# FSQCallTelemetry.net
KiCad netlist of a schematic drawn in EAGLE
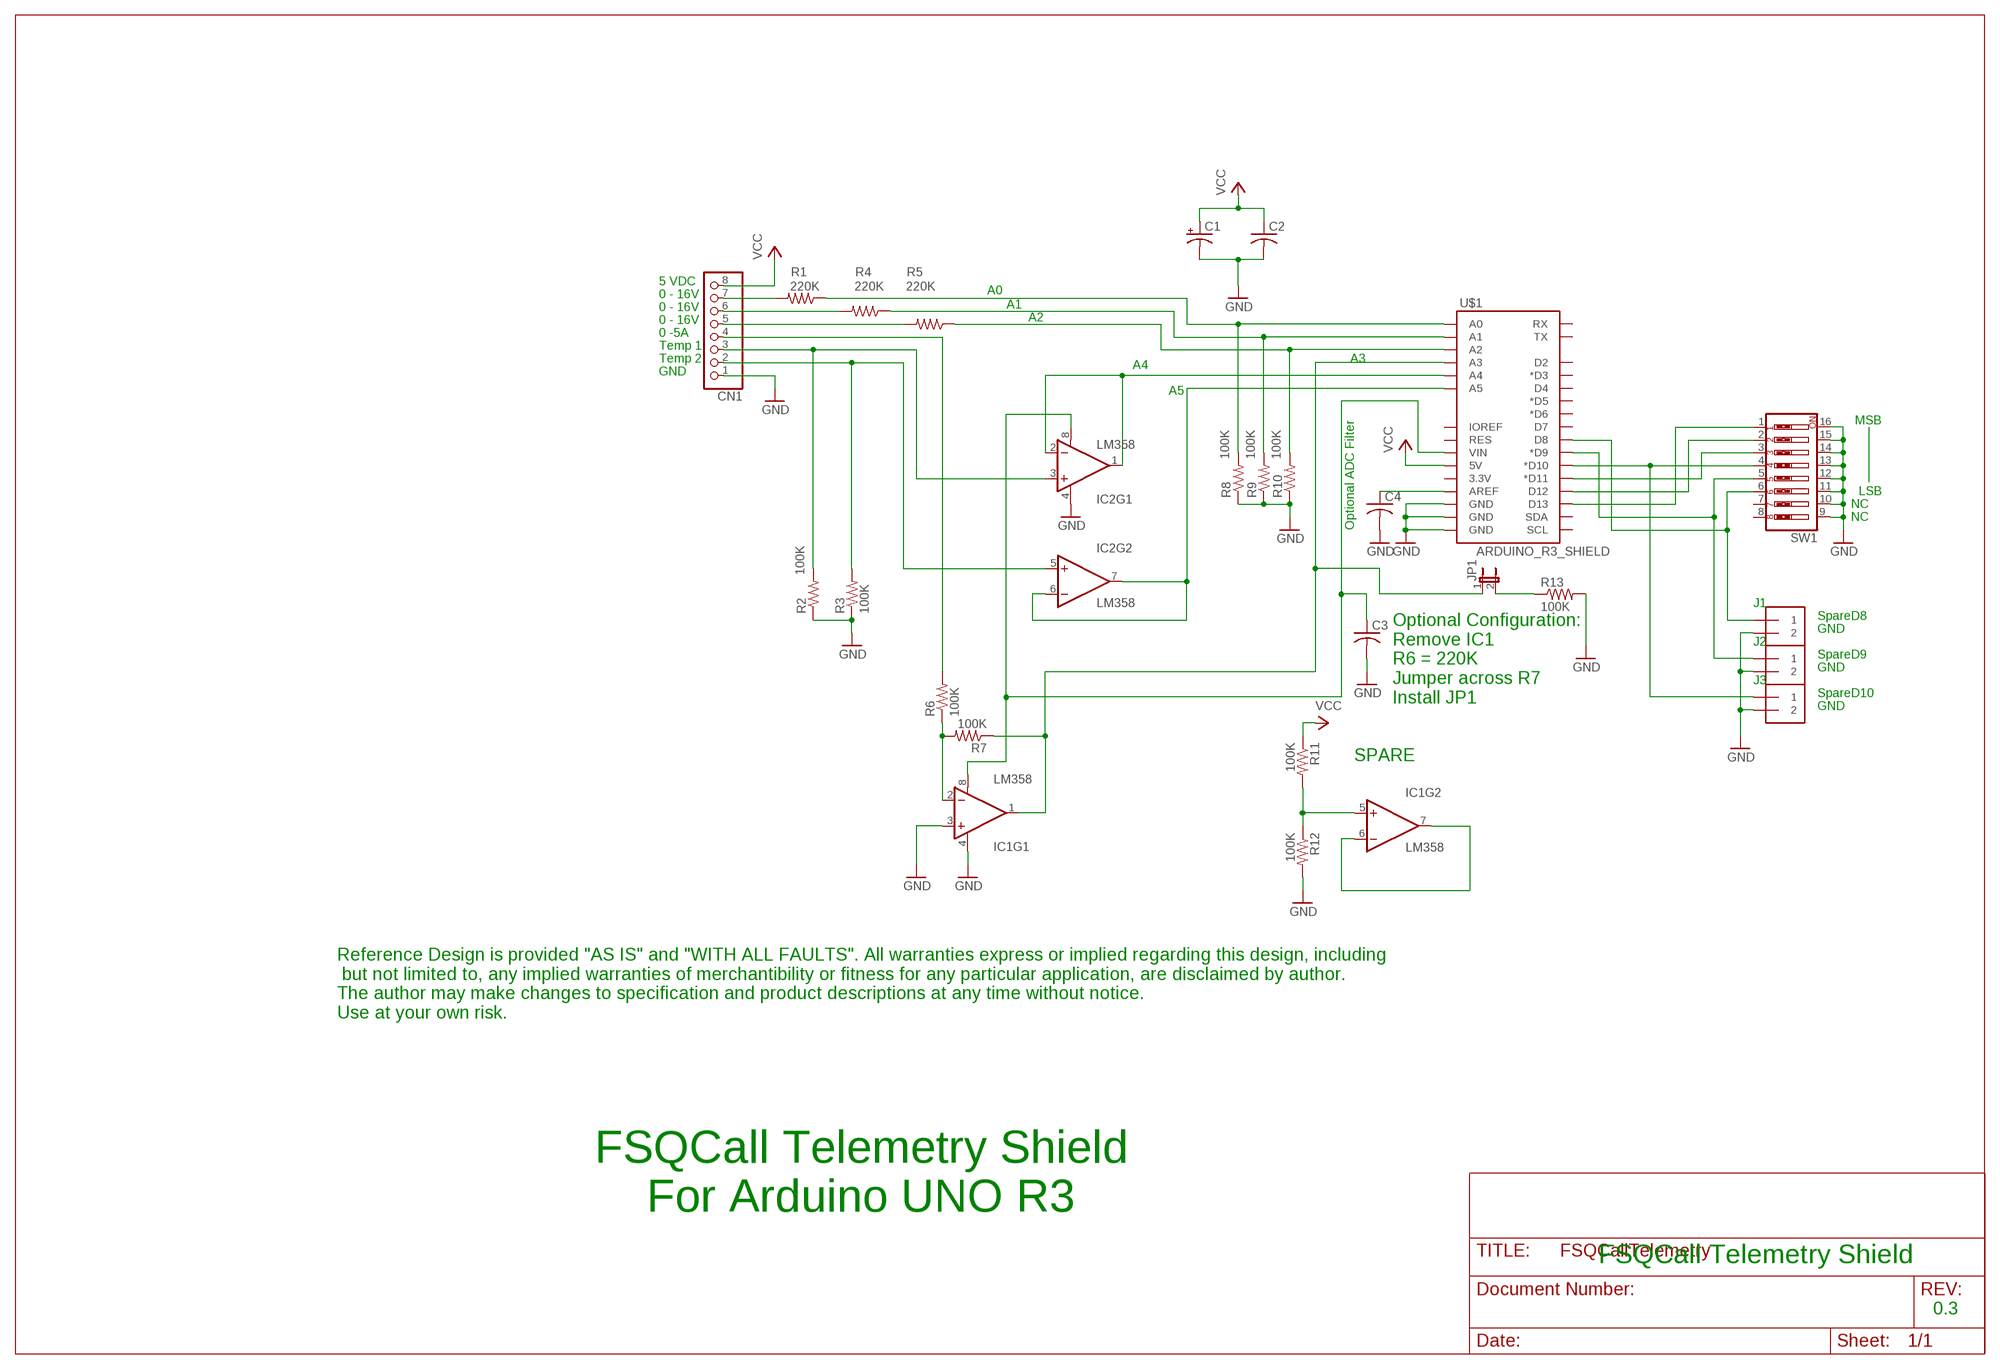
[diagram p0: schematic, sheet 1]

(export (version "E")
  (design (tool "Eeschema 10.0.6"))
  (components
    (comp (ref "C1")
      (value "CPOL-USTT6D6")
      (footprint "eagle-import:TT5D6")
      (libsource (lib "eagle-import") (part "CPOL-USTT6D6"))
    )
    (comp (ref "C2")
      (value "C-US050-025X075")
      (footprint "eagle-import:C050-025X075")
      (libsource (lib "eagle-import") (part "C-US050-025X075"))
    )
    (comp (ref "C3")
      (value "C-US050-025X075")
      (footprint "eagle-import:C050-025X075")
      (libsource (lib "eagle-import") (part "C-US050-025X075"))
    )
    (comp (ref "C4")
      (value "C-US050-025X075")
      (footprint "eagle-import:C050-025X075")
      (libsource (lib "eagle-import") (part "C-US050-025X075"))
    )
    (comp (ref "CN1")
      (value "PINHD-1X8BIG")
      (footprint "eagle-import:1X08-BIG")
      (libsource (lib "eagle-import") (part "PINHD-1X8BIG"))
    )
    (comp (ref "IC1")
      (value "LM358")
      (footprint "eagle-import:DIP08")
      (libsource (lib "eagle-import") (part "LM358"))
    )
    (comp (ref "IC2")
      (value "LM358")
      (footprint "eagle-import:DIP08")
      (libsource (lib "eagle-import") (part "LM358"))
    )
    (comp (ref "J1")
      (value "1X2-3.5MM")
      (footprint "eagle-import:1X2-3.5MM")
      (libsource (lib "eagle-import") (part "1X2-3.5MM"))
    )
    (comp (ref "J2")
      (value "1X2-3.5MM")
      (footprint "eagle-import:1X2-3.5MM")
      (libsource (lib "eagle-import") (part "1X2-3.5MM"))
    )
    (comp (ref "J3")
      (value "1X2-3.5MM")
      (footprint "eagle-import:1X2-3.5MM")
      (libsource (lib "eagle-import") (part "1X2-3.5MM"))
    )
    (comp (ref "JP1")
      (value "JP1E")
      (footprint "eagle-import:JP1")
      (libsource (lib "eagle-import") (part "JP1E"))
    )
    (comp (ref "R1")
      (value "220K")
      (footprint "eagle-import:0207_10")
      (libsource (lib "eagle-import") (part "R-US_0207/10"))
    )
    (comp (ref "R2")
      (value "100K")
      (footprint "eagle-import:0207_10")
      (libsource (lib "eagle-import") (part "R-US_0207/10"))
    )
    (comp (ref "R3")
      (value "100K")
      (footprint "eagle-import:0207_10")
      (libsource (lib "eagle-import") (part "R-US_0207/10"))
    )
    (comp (ref "R4")
      (value "220K")
      (footprint "eagle-import:0207_10")
      (libsource (lib "eagle-import") (part "R-US_0207/10"))
    )
    (comp (ref "R5")
      (value "220K")
      (footprint "eagle-import:0207_10")
      (libsource (lib "eagle-import") (part "R-US_0207/10"))
    )
    (comp (ref "R6")
      (value "100K")
      (footprint "eagle-import:0207_10")
      (libsource (lib "eagle-import") (part "R-US_0207/10"))
    )
    (comp (ref "R7")
      (value "100K")
      (footprint "eagle-import:0207_10")
      (libsource (lib "eagle-import") (part "R-US_0207/10"))
    )
    (comp (ref "R8")
      (value "100K")
      (footprint "eagle-import:0207_10")
      (libsource (lib "eagle-import") (part "R-US_0207/10"))
    )
    (comp (ref "R9")
      (value "100K")
      (footprint "eagle-import:0207_10")
      (libsource (lib "eagle-import") (part "R-US_0207/10"))
    )
    (comp (ref "R10")
      (value "100K")
      (footprint "eagle-import:0207_10")
      (libsource (lib "eagle-import") (part "R-US_0207/10"))
    )
    (comp (ref "R11")
      (value "100K")
      (footprint "eagle-import:0207_10")
      (libsource (lib "eagle-import") (part "R-US_0207/10"))
    )
    (comp (ref "R12")
      (value "100K")
      (footprint "eagle-import:0207_10")
      (libsource (lib "eagle-import") (part "R-US_0207/10"))
    )
    (comp (ref "R13")
      (value "100K")
      (footprint "eagle-import:0207_10")
      (libsource (lib "eagle-import") (part "R-US_0207/10"))
    )
    (comp (ref "SW1")
      (value "SW_DIP-8")
      (footprint "eagle-import:DIPSWITCH-08")
      (libsource (lib "eagle-import") (part "SW_DIP-8"))
    )
    (comp (ref "U$1")
      (value "ARDUINO_R3_SHIELD")
      (footprint "eagle-import:UNO_R3_SHIELD")
      (libsource (lib "eagle-import") (part "ARDUINO_R3_SHIELD"))
    )
  )
  (nets
    (net (code "1") (name "GND") (class "Default")
      (node (ref "C1") (pin "-") (pinfunction "-_-") (pintype "passive"))
      (node (ref "C2") (pin "2") (pinfunction "2_2") (pintype "passive"))
      (node (ref "C3") (pin "2") (pinfunction "2_2") (pintype "passive"))
      (node (ref "C4") (pin "2") (pinfunction "2_2") (pintype "passive"))
      (node (ref "CN1") (pin "1") (pinfunction "1_1") (pintype "passive"))
      (node (ref "IC1") (pin "3") (pinfunction "+IN_3") (pintype "input"))
      (node (ref "IC1") (pin "4") (pinfunction "V-_4") (pintype "power_in"))
      (node (ref "IC2") (pin "4") (pinfunction "V-_4") (pintype "power_in"))
      (node (ref "J1") (pin "2") (pinfunction "2_2") (pintype "passive"))
      (node (ref "J2") (pin "2") (pinfunction "2_2") (pintype "passive"))
      (node (ref "J3") (pin "2") (pinfunction "2_2") (pintype "passive"))
      (node (ref "R10") (pin "1") (pinfunction "1_1") (pintype "passive"))
      (node (ref "R12") (pin "2") (pinfunction "2_2") (pintype "passive"))
      (node (ref "R13") (pin "2") (pinfunction "2_2") (pintype "passive"))
      (node (ref "R2") (pin "1") (pinfunction "1_1") (pintype "passive"))
      (node (ref "R3") (pin "1") (pinfunction "1_1") (pintype "passive"))
      (node (ref "R8") (pin "1") (pinfunction "1_1") (pintype "passive"))
      (node (ref "R9") (pin "1") (pinfunction "1_1") (pintype "passive"))
      (node (ref "SW1") (pin "10") (pinfunction "10_10") (pintype "passive"))
      (node (ref "SW1") (pin "11") (pinfunction "11_11") (pintype "passive"))
      (node (ref "SW1") (pin "12") (pinfunction "12_12") (pintype "passive"))
      (node (ref "SW1") (pin "13") (pinfunction "13_13") (pintype "passive"))
      (node (ref "SW1") (pin "14") (pinfunction "14_14") (pintype "passive"))
      (node (ref "SW1") (pin "15") (pinfunction "15_15") (pintype "passive"))
      (node (ref "SW1") (pin "16") (pinfunction "16_16") (pintype "passive"))
      (node (ref "SW1") (pin "9") (pinfunction "9_9") (pintype "passive"))
      (node (ref "U$1") (pin "GND@0") (pinfunction "GND_GND@0") (pintype "bidirectional"))
      (node (ref "U$1") (pin "GND@1") (pinfunction "GND_GND@1") (pintype "bidirectional"))
      (node (ref "U$1") (pin "GND@2") (pinfunction "GND_GND@2") (pintype "bidirectional"))
    )
    (net (code "2") (name "Net-(C4-Pad1)") (class "Default")
      (node (ref "C4") (pin "1") (pinfunction "1_1") (pintype "passive"))
      (node (ref "U$1") (pin "AREF") (pinfunction "AREF_AREF") (pintype "bidirectional"))
    )
    (net (code "3") (name "Net-(CN1-Pad4)") (class "Default")
      (node (ref "CN1") (pin "4") (pinfunction "4_4") (pintype "passive"))
      (node (ref "R6") (pin "2") (pinfunction "2_2") (pintype "passive"))
    )
    (net (code "4") (name "Net-(CN1-Pad5)") (class "Default")
      (node (ref "CN1") (pin "5") (pinfunction "5_5") (pintype "passive"))
      (node (ref "R5") (pin "2") (pinfunction "2_2") (pintype "passive"))
    )
    (net (code "5") (name "Net-(CN1-Pad6)") (class "Default")
      (node (ref "CN1") (pin "6") (pinfunction "6_6") (pintype "passive"))
      (node (ref "R4") (pin "2") (pinfunction "2_2") (pintype "passive"))
    )
    (net (code "6") (name "Net-(CN1-Pad7)") (class "Default")
      (node (ref "CN1") (pin "7") (pinfunction "7_7") (pintype "passive"))
      (node (ref "R1") (pin "2") (pinfunction "2_2") (pintype "passive"))
    )
    (net (code "7") (name "Net-(IC1A--IN)") (class "Default")
      (node (ref "IC1") (pin "2") (pinfunction "-IN_2") (pintype "input"))
      (node (ref "R6") (pin "1") (pinfunction "1_1") (pintype "passive"))
      (node (ref "R7") (pin "2") (pinfunction "2_2") (pintype "passive"))
    )
    (net (code "8") (name "Net-(IC1A-OUT)") (class "Default")
      (node (ref "IC1") (pin "1") (pinfunction "OUT_1") (pintype "output"))
      (node (ref "JP1") (pin "1") (pinfunction "1_1") (pintype "passive"))
      (node (ref "R7") (pin "1") (pinfunction "1_1") (pintype "passive"))
      (node (ref "U$1") (pin "A3") (pinfunction "A3_A3") (pintype "bidirectional"))
    )
    (net (code "9") (name "Net-(IC1A-V+)") (class "Default")
      (node (ref "C3") (pin "1") (pinfunction "1_1") (pintype "passive"))
      (node (ref "IC1") (pin "8") (pinfunction "V+_8") (pintype "power_in"))
      (node (ref "IC2") (pin "8") (pinfunction "V+_8") (pintype "power_in"))
      (node (ref "U$1") (pin "VIN") (pinfunction "VIN_VIN") (pintype "bidirectional"))
    )
    (net (code "10") (name "Net-(IC1B-+IN)") (class "Default")
      (node (ref "IC1") (pin "5") (pinfunction "+IN_5") (pintype "input"))
      (node (ref "R11") (pin "2") (pinfunction "2_2") (pintype "passive"))
      (node (ref "R12") (pin "1") (pinfunction "1_1") (pintype "passive"))
    )
    (net (code "11") (name "Net-(IC1B--IN)") (class "Default")
      (node (ref "IC1") (pin "6") (pinfunction "-IN_6") (pintype "input"))
      (node (ref "IC1") (pin "7") (pinfunction "OUT_7") (pintype "output"))
    )
    (net (code "12") (name "Net-(IC2A-+IN)") (class "Default")
      (node (ref "CN1") (pin "3") (pinfunction "3_3") (pintype "passive"))
      (node (ref "IC2") (pin "3") (pinfunction "+IN_3") (pintype "input"))
      (node (ref "R2") (pin "2") (pinfunction "2_2") (pintype "passive"))
    )
    (net (code "13") (name "Net-(IC2A--IN)") (class "Default")
      (node (ref "IC2") (pin "1") (pinfunction "OUT_1") (pintype "output"))
      (node (ref "IC2") (pin "2") (pinfunction "-IN_2") (pintype "input"))
      (node (ref "U$1") (pin "A4") (pinfunction "A4_A4") (pintype "bidirectional"))
    )
    (net (code "14") (name "Net-(IC2B-+IN)") (class "Default")
      (node (ref "CN1") (pin "2") (pinfunction "2_2") (pintype "passive"))
      (node (ref "IC2") (pin "5") (pinfunction "+IN_5") (pintype "input"))
      (node (ref "R3") (pin "2") (pinfunction "2_2") (pintype "passive"))
    )
    (net (code "15") (name "Net-(IC2B--IN)") (class "Default")
      (node (ref "IC2") (pin "6") (pinfunction "-IN_6") (pintype "input"))
      (node (ref "IC2") (pin "7") (pinfunction "OUT_7") (pintype "output"))
      (node (ref "U$1") (pin "A5") (pinfunction "A5_A5") (pintype "bidirectional"))
    )
    (net (code "16") (name "Net-(J1-Pad1)") (class "Default")
      (node (ref "J1") (pin "1") (pinfunction "1_1") (pintype "passive"))
      (node (ref "SW1") (pin "6") (pinfunction "6_6") (pintype "passive"))
      (node (ref "U$1") (pin "D8") (pinfunction "D8_D8") (pintype "bidirectional"))
    )
    (net (code "17") (name "Net-(JP1-Pad2)") (class "Default")
      (node (ref "JP1") (pin "2") (pinfunction "2_2") (pintype "passive"))
      (node (ref "R13") (pin "1") (pinfunction "1_1") (pintype "passive"))
    )
    (net (code "18") (name "Net-(R1-Pad1)") (class "Default")
      (node (ref "R1") (pin "1") (pinfunction "1_1") (pintype "passive"))
      (node (ref "R8") (pin "2") (pinfunction "2_2") (pintype "passive"))
      (node (ref "U$1") (pin "A0") (pinfunction "A0_A0") (pintype "bidirectional"))
    )
    (net (code "19") (name "Net-(R4-Pad1)") (class "Default")
      (node (ref "R4") (pin "1") (pinfunction "1_1") (pintype "passive"))
      (node (ref "R9") (pin "2") (pinfunction "2_2") (pintype "passive"))
      (node (ref "U$1") (pin "A1") (pinfunction "A1_A1") (pintype "bidirectional"))
    )
    (net (code "20") (name "Net-(R10-Pad2)") (class "Default")
      (node (ref "R10") (pin "2") (pinfunction "2_2") (pintype "passive"))
      (node (ref "R5") (pin "1") (pinfunction "1_1") (pintype "passive"))
      (node (ref "U$1") (pin "A2") (pinfunction "A2_A2") (pintype "bidirectional"))
    )
    (net (code "21") (name "Net-(SW1-Pad1)") (class "Default")
      (node (ref "SW1") (pin "1") (pinfunction "1_1") (pintype "passive"))
      (node (ref "U$1") (pin "D13") (pinfunction "D13_D13") (pintype "bidirectional"))
    )
    (net (code "22") (name "Net-(SW1-Pad2)") (class "Default")
      (node (ref "SW1") (pin "2") (pinfunction "2_2") (pintype "passive"))
      (node (ref "U$1") (pin "D12") (pinfunction "D12_D12") (pintype "bidirectional"))
    )
    (net (code "23") (name "Net-(U$1-*D9)") (class "Default")
      (node (ref "J2") (pin "1") (pinfunction "1_1") (pintype "passive"))
      (node (ref "SW1") (pin "5") (pinfunction "5_5") (pintype "passive"))
      (node (ref "U$1") (pin "D9") (pinfunction "*D9_D9") (pintype "bidirectional"))
    )
    (net (code "24") (name "Net-(U$1-*D10)") (class "Default")
      (node (ref "J3") (pin "1") (pinfunction "1_1") (pintype "passive"))
      (node (ref "SW1") (pin "4") (pinfunction "4_4") (pintype "passive"))
      (node (ref "U$1") (pin "D10") (pinfunction "*D10_D10") (pintype "bidirectional"))
    )
    (net (code "25") (name "Net-(U$1-*D11)") (class "Default")
      (node (ref "SW1") (pin "3") (pinfunction "3_3") (pintype "passive"))
      (node (ref "U$1") (pin "D11") (pinfunction "*D11_D11") (pintype "bidirectional"))
    )
    (net (code "26") (name "VCC") (class "Default")
      (node (ref "C1") (pin "+") (pinfunction "+_+") (pintype "passive"))
      (node (ref "C2") (pin "1") (pinfunction "1_1") (pintype "passive"))
      (node (ref "CN1") (pin "8") (pinfunction "8_8") (pintype "passive"))
      (node (ref "R11") (pin "1") (pinfunction "1_1") (pintype "passive"))
      (node (ref "U$1") (pin "5V") (pinfunction "5V_5V") (pintype "bidirectional"))
    )
    (net (code "27") (name "unconnected-(SW1-Pad7)") (class "Default")
      (node (ref "SW1") (pin "7") (pinfunction "7_7") (pintype "passive"))
    )
    (net (code "28") (name "unconnected-(SW1-Pad8)") (class "Default")
      (node (ref "SW1") (pin "8") (pinfunction "8_8") (pintype "passive"))
    )
    (net (code "29") (name "unconnected-(U$1-*D3-PadD3)") (class "Default")
      (node (ref "U$1") (pin "D3") (pinfunction "*D3_D3") (pintype "bidirectional"))
    )
    (net (code "30") (name "unconnected-(U$1-*D5-PadD5)") (class "Default")
      (node (ref "U$1") (pin "D5") (pinfunction "*D5_D5") (pintype "bidirectional"))
    )
    (net (code "31") (name "unconnected-(U$1-*D6-PadD6)") (class "Default")
      (node (ref "U$1") (pin "D6") (pinfunction "*D6_D6") (pintype "bidirectional"))
    )
    (net (code "32") (name "unconnected-(U$1-Pad3.3V)") (class "Default")
      (node (ref "U$1") (pin "3.3V") (pinfunction "3.3V_3.3V") (pintype "bidirectional"))
    )
    (net (code "33") (name "unconnected-(U$1-PadD2)") (class "Default")
      (node (ref "U$1") (pin "D2") (pinfunction "D2_D2") (pintype "bidirectional"))
    )
    (net (code "34") (name "unconnected-(U$1-PadD4)") (class "Default")
      (node (ref "U$1") (pin "D4") (pinfunction "D4_D4") (pintype "bidirectional"))
    )
    (net (code "35") (name "unconnected-(U$1-PadD7)") (class "Default")
      (node (ref "U$1") (pin "D7") (pinfunction "D7_D7") (pintype "bidirectional"))
    )
    (net (code "36") (name "unconnected-(U$1-PadIOREF)") (class "Default")
      (node (ref "U$1") (pin "IOREF") (pinfunction "IOREF_IOREF") (pintype "bidirectional"))
    )
    (net (code "37") (name "unconnected-(U$1-PadRES)") (class "Default")
      (node (ref "U$1") (pin "RES") (pinfunction "RES_RES") (pintype "bidirectional"))
    )
    (net (code "38") (name "unconnected-(U$1-PadRX)") (class "Default")
      (node (ref "U$1") (pin "RX") (pinfunction "RX_RX") (pintype "bidirectional"))
    )
    (net (code "39") (name "unconnected-(U$1-PadSCL)") (class "Default")
      (node (ref "U$1") (pin "SCL") (pinfunction "SCL_SCL") (pintype "bidirectional"))
    )
    (net (code "40") (name "unconnected-(U$1-PadSDA)") (class "Default")
      (node (ref "U$1") (pin "SDA") (pinfunction "SDA_SDA") (pintype "bidirectional"))
    )
    (net (code "41") (name "unconnected-(U$1-PadTX)") (class "Default")
      (node (ref "U$1") (pin "TX") (pinfunction "TX_TX") (pintype "bidirectional"))
    )
  )
)
